# STM32F103ZGT6.net
KiCad netlist of a schematic drawn in Altium Designer
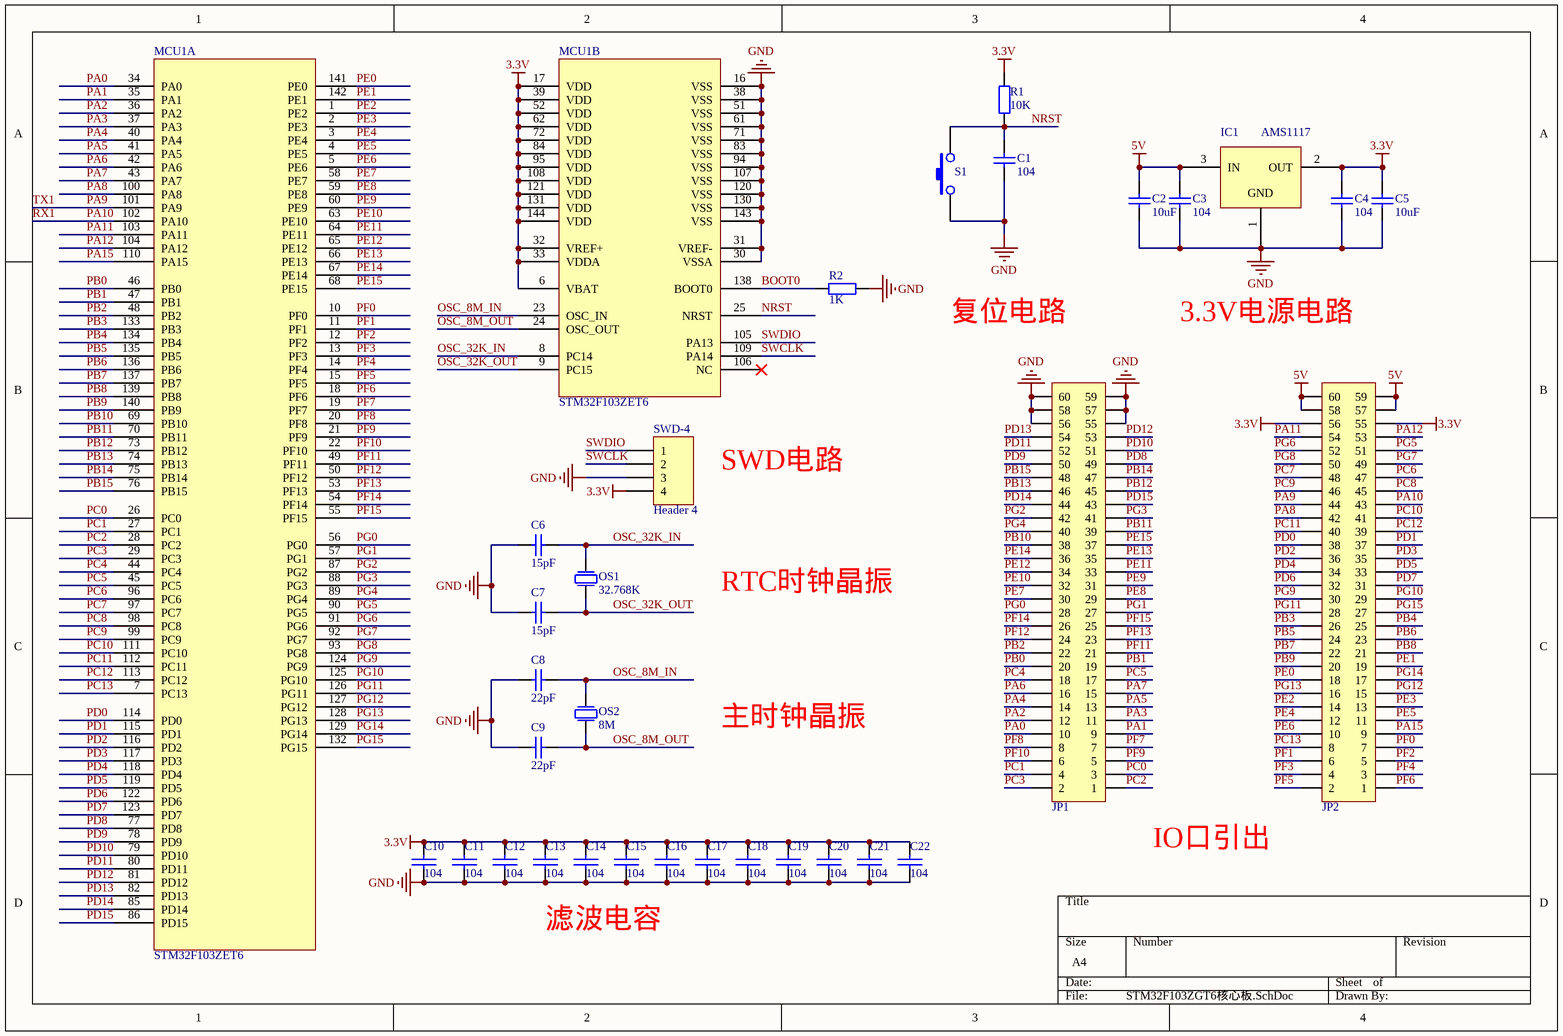
[diagram p0: STM32F103ZGT6核心板.SchDoc]

(export (version "E")
  (design (tool "Eeschema 10.0.6"))
  (components
    (comp (ref "C1") (value "104") (footprint "C 0603_L") (libsource (lib "零散元件库") (part "Cap1")))
    (comp (ref "C2") (value "10uF") (footprint "C 0603_L") (libsource (lib "零散元件库") (part "Cap1")))
    (comp (ref "C3") (value "104") (footprint "C 0603_L") (libsource (lib "零散元件库") (part "Cap1")))
    (comp (ref "C4") (value "104") (footprint "C 0603_L") (libsource (lib "零散元件库") (part "Cap1")))
    (comp (ref "C5") (value "10uF") (footprint "C 0603_L") (libsource (lib "零散元件库") (part "Cap1")))
    (comp (ref "C6") (value "15pF") (footprint "C 0603_L") (libsource (lib "零散元件库") (part "Cap1")))
    (comp (ref "C7") (value "15pF") (footprint "C 0603_L") (libsource (lib "零散元件库") (part "Cap1")))
    (comp (ref "C8") (value "22pF") (footprint "C 0603_L") (libsource (lib "零散元件库") (part "Cap1")))
    (comp (ref "C9") (value "22pF") (footprint "C 0603_L") (libsource (lib "零散元件库") (part "Cap1")))
    (comp (ref "C10")
      (value "104")
      (footprint "C 0603_L")
      (description "Capacitor")
      (libsource (lib "*") (part "CAP"))
    )
    (comp (ref "C11")
      (value "104")
      (footprint "C 0603_L")
      (description "Capacitor")
      (libsource (lib "*") (part "CAP"))
    )
    (comp (ref "C12")
      (value "104")
      (footprint "C 0603_L")
      (description "Capacitor")
      (libsource (lib "*") (part "CAP"))
    )
    (comp (ref "C13")
      (value "104")
      (footprint "C 0603_L")
      (description "Capacitor")
      (libsource (lib "*") (part "CAP"))
    )
    (comp (ref "C14")
      (value "104")
      (footprint "C 0603_L")
      (description "Capacitor")
      (libsource (lib "*") (part "CAP"))
    )
    (comp (ref "C15")
      (value "104")
      (footprint "C 0603_L")
      (description "Capacitor")
      (libsource (lib "*") (part "CAP"))
    )
    (comp (ref "C16")
      (value "104")
      (footprint "C 0603_L")
      (description "Capacitor")
      (libsource (lib "*") (part "CAP"))
    )
    (comp (ref "C17")
      (value "104")
      (footprint "C 0603_L")
      (description "Capacitor")
      (libsource (lib "*") (part "CAP"))
    )
    (comp (ref "C18")
      (value "104")
      (footprint "C 0603_L")
      (description "Capacitor")
      (libsource (lib "*") (part "CAP"))
    )
    (comp (ref "C19")
      (value "104")
      (footprint "C 0603_L")
      (description "Capacitor")
      (libsource (lib "*") (part "CAP"))
    )
    (comp (ref "C20")
      (value "104")
      (footprint "C 0603_L")
      (description "Capacitor")
      (libsource (lib "*") (part "CAP"))
    )
    (comp (ref "C21")
      (value "104")
      (footprint "C 0603_L")
      (description "Capacitor")
      (libsource (lib "*") (part "CAP"))
    )
    (comp (ref "C22")
      (value "104")
      (footprint "C 0603_L")
      (description "Capacitor")
      (libsource (lib "*") (part "CAP"))
    )
    (comp (ref "IC1") (value "AMS1117") (footprint "SOT89") (libsource (lib "零散元件库") (part "CJA1117")))
    (comp (ref "JP1")
      (value "Header 2X30")
      (footprint "HDR-SMD_60P-P1.27-V-M-R2-C30-LS5.8")
      (description "30*2P接插件")
      (fields (field (name "版权归属") "封装库来自淘宝 ID：黄晶宝石"))
      (libsource (lib "5.4 - 接插件-脚距2.54 (100mil) ") (part "Header 30X2"))
    )
    (comp (ref "JP2")
      (value "Header 2X30")
      (footprint "HDR-SMD_60P-P1.27-V-M-R2-C30-LS5.8")
      (description "30*2P接插件")
      (fields (field (name "版权归属") "封装库来自淘宝 ID：黄晶宝石"))
      (libsource (lib "5.4 - 接插件-脚距2.54 (100mil) ") (part "Header 30X2"))
    )
    (comp (ref "MCU1")
      (value "STM32F103ZET6")
      (footprint "F-QFP20x20-G144/Z24N")
      (libsource (lib "零散元件库") (part "STM32F103ZET6"))
    )
    (comp (ref "OS1")
      (value "32.768K")
      (footprint "R 0805_M")
      (fields (field (name "VAULE") "32.768K"))
      (libsource (lib "零散元件库") (part "晶振"))
    )
    (comp (ref "OS2")
      (value "8M")
      (footprint "OSC 5032-2P")
      (fields (field (name "VAULE") "8M"))
      (libsource (lib "零散元件库") (part "晶振"))
    )
    (comp (ref "R1") (value "10K") (footprint "R 0603_L") (libsource (lib "") (part "Res_1")))
    (comp (ref "R2") (value "1K") (footprint "R 0603_L") (libsource (lib "零散元件库") (part "Res")))
    (comp (ref "S1") (value "KEY") (footprint "SWT3*4") (libsource (lib "CCDXPLIB") (part "KEY")))
    (comp (ref "SWD-4")
      (value "Header 4")
      (footprint "HDR1X4")
      (description "Header, 4-Pin")
      (fields (field (name "PUBLISHER") "Altium Limited"))
      (libsource (lib "Miscellaneous Connectors") (part "Header 4"))
    )
  )
  (nets
    (net (code "2") (name "/BOOT0") (class "Default")
      (node (ref "MCU1") (pin "138") (pinfunction "BOOT0_138") (pintype "passive"))
      (node (ref "R2") (pin "2") (pinfunction "2_2") (pintype "passive"))
    )
    (net (code "3") (name "/NRST") (class "Default")
      (node (ref "C1") (pin "2") (pinfunction "2_2") (pintype "passive"))
      (node (ref "MCU1") (pin "25") (pinfunction "NRST_25") (pintype "passive"))
      (node (ref "R1") (pin "1") (pinfunction "1_1") (pintype "passive"))
      (node (ref "S1") (pin "2") (pinfunction "2_2") (pintype "passive"))
    )
    (net (code "4") (name "/OSC_8M_IN") (class "Default")
      (node (ref "C8") (pin "1") (pinfunction "1_1") (pintype "passive"))
      (node (ref "MCU1") (pin "23") (pinfunction "OSC_IN_23") (pintype "passive"))
      (node (ref "OS2") (pin "1") (pinfunction "P1_1") (pintype "passive"))
    )
    (net (code "5") (name "/OSC_8M_OUT") (class "Default")
      (node (ref "C9") (pin "1") (pinfunction "1_1") (pintype "passive"))
      (node (ref "MCU1") (pin "24") (pinfunction "OSC_OUT_24") (pintype "passive"))
      (node (ref "OS2") (pin "2") (pinfunction "P2_2") (pintype "passive"))
    )
    (net (code "6") (name "/OSC_32K_IN") (class "Default")
      (node (ref "C6") (pin "1") (pinfunction "1_1") (pintype "passive"))
      (node (ref "MCU1") (pin "8") (pinfunction "PC14_8") (pintype "passive"))
      (node (ref "OS1") (pin "1") (pinfunction "P1_1") (pintype "passive"))
    )
    (net (code "7") (name "/OSC_32K_OUT") (class "Default")
      (node (ref "C7") (pin "1") (pinfunction "1_1") (pintype "passive"))
      (node (ref "MCU1") (pin "9") (pinfunction "PC15_9") (pintype "passive"))
      (node (ref "OS1") (pin "2") (pinfunction "P2_2") (pintype "passive"))
    )
    (net (code "8") (name "/PA0") (class "Default")
      (node (ref "JP1") (pin "10") (pinfunction "10_10") (pintype "passive"))
      (node (ref "MCU1") (pin "34") (pinfunction "PA0_34") (pintype "passive"))
    )
    (net (code "9") (name "/PA1") (class "Default")
      (node (ref "JP1") (pin "9") (pinfunction "9_9") (pintype "passive"))
      (node (ref "MCU1") (pin "35") (pinfunction "PA1_35") (pintype "passive"))
    )
    (net (code "10") (name "/PA2") (class "Default")
      (node (ref "JP1") (pin "12") (pinfunction "12_12") (pintype "passive"))
      (node (ref "MCU1") (pin "36") (pinfunction "PA2_36") (pintype "passive"))
    )
    (net (code "11") (name "/PA3") (class "Default")
      (node (ref "JP1") (pin "11") (pinfunction "11_11") (pintype "passive"))
      (node (ref "MCU1") (pin "37") (pinfunction "PA3_37") (pintype "passive"))
    )
    (net (code "12") (name "/PA4") (class "Default")
      (node (ref "JP1") (pin "14") (pinfunction "14_14") (pintype "passive"))
      (node (ref "MCU1") (pin "40") (pinfunction "PA4_40") (pintype "passive"))
    )
    (net (code "13") (name "/PA5") (class "Default")
      (node (ref "JP1") (pin "13") (pinfunction "13_13") (pintype "passive"))
      (node (ref "MCU1") (pin "41") (pinfunction "PA5_41") (pintype "passive"))
    )
    (net (code "14") (name "/PA6") (class "Default")
      (node (ref "JP1") (pin "16") (pinfunction "16_16") (pintype "passive"))
      (node (ref "MCU1") (pin "42") (pinfunction "PA6_42") (pintype "passive"))
    )
    (net (code "15") (name "/PA7") (class "Default")
      (node (ref "JP1") (pin "15") (pinfunction "15_15") (pintype "passive"))
      (node (ref "MCU1") (pin "43") (pinfunction "PA7_43") (pintype "passive"))
    )
    (net (code "16") (name "/PA8") (class "Default")
      (node (ref "JP2") (pin "42") (pinfunction "42_42") (pintype "passive"))
      (node (ref "MCU1") (pin "100") (pinfunction "PA8_100") (pintype "passive"))
    )
    (net (code "17") (name "/PA9") (class "Default")
      (node (ref "JP2") (pin "44") (pinfunction "44_44") (pintype "passive"))
      (node (ref "MCU1") (pin "101") (pinfunction "PA9_101") (pintype "passive"))
    )
    (net (code "18") (name "/PA10") (class "Default")
      (node (ref "JP2") (pin "43") (pinfunction "43_43") (pintype "passive"))
      (node (ref "MCU1") (pin "102") (pinfunction "PA10_102") (pintype "passive"))
    )
    (net (code "19") (name "/PA11") (class "Default")
      (node (ref "JP2") (pin "54") (pinfunction "54_54") (pintype "passive"))
      (node (ref "MCU1") (pin "103") (pinfunction "PA11_103") (pintype "passive"))
    )
    (net (code "20") (name "/PA12") (class "Default")
      (node (ref "JP2") (pin "53") (pinfunction "53_53") (pintype "passive"))
      (node (ref "MCU1") (pin "104") (pinfunction "PA12_104") (pintype "passive"))
    )
    (net (code "21") (name "/PA15") (class "Default")
      (node (ref "JP2") (pin "9") (pinfunction "9_9") (pintype "passive"))
      (node (ref "MCU1") (pin "110") (pinfunction "PA15_110") (pintype "passive"))
    )
    (net (code "22") (name "/PB0") (class "Default")
      (node (ref "JP1") (pin "20") (pinfunction "20_20") (pintype "passive"))
      (node (ref "MCU1") (pin "46") (pinfunction "PB0_46") (pintype "passive"))
    )
    (net (code "23") (name "/PB1") (class "Default")
      (node (ref "JP1") (pin "19") (pinfunction "19_19") (pintype "passive"))
      (node (ref "MCU1") (pin "47") (pinfunction "PB1_47") (pintype "passive"))
    )
    (net (code "24") (name "/PB2") (class "Default")
      (node (ref "JP1") (pin "22") (pinfunction "22_22") (pintype "passive"))
      (node (ref "MCU1") (pin "48") (pinfunction "PB2_48") (pintype "passive"))
    )
    (net (code "25") (name "/PB3") (class "Default")
      (node (ref "JP2") (pin "26") (pinfunction "26_26") (pintype "passive"))
      (node (ref "MCU1") (pin "133") (pinfunction "PB3_133") (pintype "passive"))
    )
    (net (code "26") (name "/PB4") (class "Default")
      (node (ref "JP2") (pin "25") (pinfunction "25_25") (pintype "passive"))
      (node (ref "MCU1") (pin "134") (pinfunction "PB4_134") (pintype "passive"))
    )
    (net (code "27") (name "/PB5") (class "Default")
      (node (ref "JP2") (pin "24") (pinfunction "24_24") (pintype "passive"))
      (node (ref "MCU1") (pin "135") (pinfunction "PB5_135") (pintype "passive"))
    )
    (net (code "28") (name "/PB6") (class "Default")
      (node (ref "JP2") (pin "23") (pinfunction "23_23") (pintype "passive"))
      (node (ref "MCU1") (pin "136") (pinfunction "PB6_136") (pintype "passive"))
    )
    (net (code "29") (name "/PB7") (class "Default")
      (node (ref "JP2") (pin "22") (pinfunction "22_22") (pintype "passive"))
      (node (ref "MCU1") (pin "137") (pinfunction "PB7_137") (pintype "passive"))
    )
    (net (code "30") (name "/PB8") (class "Default")
      (node (ref "JP2") (pin "21") (pinfunction "21_21") (pintype "passive"))
      (node (ref "MCU1") (pin "139") (pinfunction "PB8_139") (pintype "passive"))
    )
    (net (code "31") (name "/PB9") (class "Default")
      (node (ref "JP2") (pin "20") (pinfunction "20_20") (pintype "passive"))
      (node (ref "MCU1") (pin "140") (pinfunction "PB9_140") (pintype "passive"))
    )
    (net (code "32") (name "/PB10") (class "Default")
      (node (ref "JP1") (pin "38") (pinfunction "38_38") (pintype "passive"))
      (node (ref "MCU1") (pin "69") (pinfunction "PB10_69") (pintype "passive"))
    )
    (net (code "33") (name "/PB11") (class "Default")
      (node (ref "JP1") (pin "39") (pinfunction "39_39") (pintype "passive"))
      (node (ref "MCU1") (pin "70") (pinfunction "PB11_70") (pintype "passive"))
    )
    (net (code "34") (name "/PB12") (class "Default")
      (node (ref "JP1") (pin "45") (pinfunction "45_45") (pintype "passive"))
      (node (ref "MCU1") (pin "73") (pinfunction "PB12_73") (pintype "passive"))
    )
    (net (code "35") (name "/PB13") (class "Default")
      (node (ref "JP1") (pin "46") (pinfunction "46_46") (pintype "passive"))
      (node (ref "MCU1") (pin "74") (pinfunction "PB13_74") (pintype "passive"))
    )
    (net (code "36") (name "/PB14") (class "Default")
      (node (ref "JP1") (pin "47") (pinfunction "47_47") (pintype "passive"))
      (node (ref "MCU1") (pin "75") (pinfunction "PB14_75") (pintype "passive"))
    )
    (net (code "37") (name "/PB15") (class "Default")
      (node (ref "JP1") (pin "48") (pinfunction "48_48") (pintype "passive"))
      (node (ref "MCU1") (pin "76") (pinfunction "PB15_76") (pintype "passive"))
    )
    (net (code "38") (name "/PC0") (class "Default")
      (node (ref "JP1") (pin "3") (pinfunction "3_3") (pintype "passive"))
      (node (ref "MCU1") (pin "26") (pinfunction "PC0_26") (pintype "passive"))
    )
    (net (code "39") (name "/PC1") (class "Default")
      (node (ref "JP1") (pin "4") (pinfunction "4_4") (pintype "passive"))
      (node (ref "MCU1") (pin "27") (pinfunction "PC1_27") (pintype "passive"))
    )
    (net (code "40") (name "/PC2") (class "Default")
      (node (ref "JP1") (pin "1") (pinfunction "1_1") (pintype "passive"))
      (node (ref "MCU1") (pin "28") (pinfunction "PC2_28") (pintype "passive"))
    )
    (net (code "41") (name "/PC3") (class "Default")
      (node (ref "JP1") (pin "2") (pinfunction "2_2") (pintype "passive"))
      (node (ref "MCU1") (pin "29") (pinfunction "PC3_29") (pintype "passive"))
    )
    (net (code "42") (name "/PC4") (class "Default")
      (node (ref "JP1") (pin "18") (pinfunction "18_18") (pintype "passive"))
      (node (ref "MCU1") (pin "44") (pinfunction "PC4_44") (pintype "passive"))
    )
    (net (code "43") (name "/PC5") (class "Default")
      (node (ref "JP1") (pin "17") (pinfunction "17_17") (pintype "passive"))
      (node (ref "MCU1") (pin "45") (pinfunction "PC5_45") (pintype "passive"))
    )
    (net (code "44") (name "/PC6") (class "Default")
      (node (ref "JP2") (pin "47") (pinfunction "47_47") (pintype "passive"))
      (node (ref "MCU1") (pin "96") (pinfunction "PC6_96") (pintype "passive"))
    )
    (net (code "45") (name "/PC7") (class "Default")
      (node (ref "JP2") (pin "48") (pinfunction "48_48") (pintype "passive"))
      (node (ref "MCU1") (pin "97") (pinfunction "PC7_97") (pintype "passive"))
    )
    (net (code "46") (name "/PC8") (class "Default")
      (node (ref "JP2") (pin "45") (pinfunction "45_45") (pintype "passive"))
      (node (ref "MCU1") (pin "98") (pinfunction "PC8_98") (pintype "passive"))
    )
    (net (code "47") (name "/PC9") (class "Default")
      (node (ref "JP2") (pin "46") (pinfunction "46_46") (pintype "passive"))
      (node (ref "MCU1") (pin "99") (pinfunction "PC9_99") (pintype "passive"))
    )
    (net (code "48") (name "/PC10") (class "Default")
      (node (ref "JP2") (pin "41") (pinfunction "41_41") (pintype "passive"))
      (node (ref "MCU1") (pin "111") (pinfunction "PC10_111") (pintype "passive"))
    )
    (net (code "49") (name "/PC11") (class "Default")
      (node (ref "JP2") (pin "40") (pinfunction "40_40") (pintype "passive"))
      (node (ref "MCU1") (pin "112") (pinfunction "PC11_112") (pintype "passive"))
    )
    (net (code "50") (name "/PC12") (class "Default")
      (node (ref "JP2") (pin "39") (pinfunction "39_39") (pintype "passive"))
      (node (ref "MCU1") (pin "113") (pinfunction "PC12_113") (pintype "passive"))
    )
    (net (code "51") (name "/PC13") (class "Default")
      (node (ref "JP2") (pin "8") (pinfunction "8_8") (pintype "passive"))
      (node (ref "MCU1") (pin "7") (pinfunction "PC13_7") (pintype "passive"))
    )
    (net (code "52") (name "/PD0") (class "Default")
      (node (ref "JP2") (pin "38") (pinfunction "38_38") (pintype "passive"))
      (node (ref "MCU1") (pin "114") (pinfunction "PD0_114") (pintype "passive"))
    )
    (net (code "53") (name "/PD1") (class "Default")
      (node (ref "JP2") (pin "37") (pinfunction "37_37") (pintype "passive"))
      (node (ref "MCU1") (pin "115") (pinfunction "PD1_115") (pintype "passive"))
    )
    (net (code "54") (name "/PD2") (class "Default")
      (node (ref "JP2") (pin "36") (pinfunction "36_36") (pintype "passive"))
      (node (ref "MCU1") (pin "116") (pinfunction "PD2_116") (pintype "passive"))
    )
    (net (code "55") (name "/PD3") (class "Default")
      (node (ref "JP2") (pin "35") (pinfunction "35_35") (pintype "passive"))
      (node (ref "MCU1") (pin "117") (pinfunction "PD3_117") (pintype "passive"))
    )
    (net (code "56") (name "/PD4") (class "Default")
      (node (ref "JP2") (pin "34") (pinfunction "34_34") (pintype "passive"))
      (node (ref "MCU1") (pin "118") (pinfunction "PD4_118") (pintype "passive"))
    )
    (net (code "57") (name "/PD5") (class "Default")
      (node (ref "JP2") (pin "33") (pinfunction "33_33") (pintype "passive"))
      (node (ref "MCU1") (pin "119") (pinfunction "PD5_119") (pintype "passive"))
    )
    (net (code "58") (name "/PD6") (class "Default")
      (node (ref "JP2") (pin "32") (pinfunction "32_32") (pintype "passive"))
      (node (ref "MCU1") (pin "122") (pinfunction "PD6_122") (pintype "passive"))
    )
    (net (code "59") (name "/PD7") (class "Default")
      (node (ref "JP2") (pin "31") (pinfunction "31_31") (pintype "passive"))
      (node (ref "MCU1") (pin "123") (pinfunction "PD7_123") (pintype "passive"))
    )
    (net (code "60") (name "/PD8") (class "Default")
      (node (ref "JP1") (pin "49") (pinfunction "49_49") (pintype "passive"))
      (node (ref "MCU1") (pin "77") (pinfunction "PD8_77") (pintype "passive"))
    )
    (net (code "61") (name "/PD9") (class "Default")
      (node (ref "JP1") (pin "50") (pinfunction "50_50") (pintype "passive"))
      (node (ref "MCU1") (pin "78") (pinfunction "PD9_78") (pintype "passive"))
    )
    (net (code "62") (name "/PD10") (class "Default")
      (node (ref "JP1") (pin "51") (pinfunction "51_51") (pintype "passive"))
      (node (ref "MCU1") (pin "79") (pinfunction "PD10_79") (pintype "passive"))
    )
    (net (code "63") (name "/PD11") (class "Default")
      (node (ref "JP1") (pin "52") (pinfunction "52_52") (pintype "passive"))
      (node (ref "MCU1") (pin "80") (pinfunction "PD11_80") (pintype "passive"))
    )
    (net (code "64") (name "/PD12") (class "Default")
      (node (ref "JP1") (pin "53") (pinfunction "53_53") (pintype "passive"))
      (node (ref "MCU1") (pin "81") (pinfunction "PD12_81") (pintype "passive"))
    )
    (net (code "65") (name "/PD13") (class "Default")
      (node (ref "JP1") (pin "54") (pinfunction "54_54") (pintype "passive"))
      (node (ref "MCU1") (pin "82") (pinfunction "PD13_82") (pintype "passive"))
    )
    (net (code "66") (name "/PD14") (class "Default")
      (node (ref "JP1") (pin "44") (pinfunction "44_44") (pintype "passive"))
      (node (ref "MCU1") (pin "85") (pinfunction "PD14_85") (pintype "passive"))
    )
    (net (code "67") (name "/PD15") (class "Default")
      (node (ref "JP1") (pin "43") (pinfunction "43_43") (pintype "passive"))
      (node (ref "MCU1") (pin "86") (pinfunction "PD15_86") (pintype "passive"))
    )
    (net (code "68") (name "/PE0") (class "Default")
      (node (ref "JP2") (pin "18") (pinfunction "18_18") (pintype "passive"))
      (node (ref "MCU1") (pin "141") (pinfunction "PE0_141") (pintype "passive"))
    )
    (net (code "69") (name "/PE1") (class "Default")
      (node (ref "JP2") (pin "19") (pinfunction "19_19") (pintype "passive"))
      (node (ref "MCU1") (pin "142") (pinfunction "PE1_142") (pintype "passive"))
    )
    (net (code "70") (name "/PE2") (class "Default")
      (node (ref "JP2") (pin "14") (pinfunction "14_14") (pintype "passive"))
      (node (ref "MCU1") (pin "1") (pinfunction "PE2_1") (pintype "passive"))
    )
    (net (code "71") (name "/PE3") (class "Default")
      (node (ref "JP2") (pin "13") (pinfunction "13_13") (pintype "passive"))
      (node (ref "MCU1") (pin "2") (pinfunction "PE3_2") (pintype "passive"))
    )
    (net (code "72") (name "/PE4") (class "Default")
      (node (ref "JP2") (pin "12") (pinfunction "12_12") (pintype "passive"))
      (node (ref "MCU1") (pin "3") (pinfunction "PE4_3") (pintype "passive"))
    )
    (net (code "73") (name "/PE5") (class "Default")
      (node (ref "JP2") (pin "11") (pinfunction "11_11") (pintype "passive"))
      (node (ref "MCU1") (pin "4") (pinfunction "PE5_4") (pintype "passive"))
    )
    (net (code "74") (name "/PE6") (class "Default")
      (node (ref "JP2") (pin "10") (pinfunction "10_10") (pintype "passive"))
      (node (ref "MCU1") (pin "5") (pinfunction "PE6_5") (pintype "passive"))
    )
    (net (code "75") (name "/PE7") (class "Default")
      (node (ref "JP1") (pin "30") (pinfunction "30_30") (pintype "passive"))
      (node (ref "MCU1") (pin "58") (pinfunction "PE7_58") (pintype "passive"))
    )
    (net (code "76") (name "/PE8") (class "Default")
      (node (ref "JP1") (pin "29") (pinfunction "29_29") (pintype "passive"))
      (node (ref "MCU1") (pin "59") (pinfunction "PE8_59") (pintype "passive"))
    )
    (net (code "77") (name "/PE9") (class "Default")
      (node (ref "JP1") (pin "31") (pinfunction "31_31") (pintype "passive"))
      (node (ref "MCU1") (pin "60") (pinfunction "PE9_60") (pintype "passive"))
    )
    (net (code "78") (name "/PE10") (class "Default")
      (node (ref "JP1") (pin "32") (pinfunction "32_32") (pintype "passive"))
      (node (ref "MCU1") (pin "63") (pinfunction "PE10_63") (pintype "passive"))
    )
    (net (code "79") (name "/PE11") (class "Default")
      (node (ref "JP1") (pin "33") (pinfunction "33_33") (pintype "passive"))
      (node (ref "MCU1") (pin "64") (pinfunction "PE11_64") (pintype "passive"))
    )
    (net (code "80") (name "/PE12") (class "Default")
      (node (ref "JP1") (pin "34") (pinfunction "34_34") (pintype "passive"))
      (node (ref "MCU1") (pin "65") (pinfunction "PE12_65") (pintype "passive"))
    )
    (net (code "81") (name "/PE13") (class "Default")
      (node (ref "JP1") (pin "35") (pinfunction "35_35") (pintype "passive"))
      (node (ref "MCU1") (pin "66") (pinfunction "PE13_66") (pintype "passive"))
    )
    (net (code "82") (name "/PE14") (class "Default")
      (node (ref "JP1") (pin "36") (pinfunction "36_36") (pintype "passive"))
      (node (ref "MCU1") (pin "67") (pinfunction "PE14_67") (pintype "passive"))
    )
    (net (code "83") (name "/PE15") (class "Default")
      (node (ref "JP1") (pin "37") (pinfunction "37_37") (pintype "passive"))
      (node (ref "MCU1") (pin "68") (pinfunction "PE15_68") (pintype "passive"))
    )
    (net (code "84") (name "/PF0") (class "Default")
      (node (ref "JP2") (pin "7") (pinfunction "7_7") (pintype "passive"))
      (node (ref "MCU1") (pin "10") (pinfunction "PF0_10") (pintype "passive"))
    )
    (net (code "85") (name "/PF1") (class "Default")
      (node (ref "JP2") (pin "6") (pinfunction "6_6") (pintype "passive"))
      (node (ref "MCU1") (pin "11") (pinfunction "PF1_11") (pintype "passive"))
    )
    (net (code "86") (name "/PF2") (class "Default")
      (node (ref "JP2") (pin "5") (pinfunction "5_5") (pintype "passive"))
      (node (ref "MCU1") (pin "12") (pinfunction "PF2_12") (pintype "passive"))
    )
    (net (code "87") (name "/PF3") (class "Default")
      (node (ref "JP2") (pin "4") (pinfunction "4_4") (pintype "passive"))
      (node (ref "MCU1") (pin "13") (pinfunction "PF3_13") (pintype "passive"))
    )
    (net (code "88") (name "/PF4") (class "Default")
      (node (ref "JP2") (pin "3") (pinfunction "3_3") (pintype "passive"))
      (node (ref "MCU1") (pin "14") (pinfunction "PF4_14") (pintype "passive"))
    )
    (net (code "89") (name "/PF5") (class "Default")
      (node (ref "JP2") (pin "2") (pinfunction "2_2") (pintype "passive"))
      (node (ref "MCU1") (pin "15") (pinfunction "PF5_15") (pintype "passive"))
    )
    (net (code "90") (name "/PF6") (class "Default")
      (node (ref "JP2") (pin "1") (pinfunction "1_1") (pintype "passive"))
      (node (ref "MCU1") (pin "18") (pinfunction "PF6_18") (pintype "passive"))
    )
    (net (code "91") (name "/PF7") (class "Default")
      (node (ref "JP1") (pin "7") (pinfunction "7_7") (pintype "passive"))
      (node (ref "MCU1") (pin "19") (pinfunction "PF7_19") (pintype "passive"))
    )
    (net (code "92") (name "/PF8") (class "Default")
      (node (ref "JP1") (pin "8") (pinfunction "8_8") (pintype "passive"))
      (node (ref "MCU1") (pin "20") (pinfunction "PF8_20") (pintype "passive"))
    )
    (net (code "93") (name "/PF9") (class "Default")
      (node (ref "JP1") (pin "5") (pinfunction "5_5") (pintype "passive"))
      (node (ref "MCU1") (pin "21") (pinfunction "PF9_21") (pintype "passive"))
    )
    (net (code "94") (name "/PF10") (class "Default")
      (node (ref "JP1") (pin "6") (pinfunction "6_6") (pintype "passive"))
      (node (ref "MCU1") (pin "22") (pinfunction "PF10_22") (pintype "passive"))
    )
    (net (code "95") (name "/PF11") (class "Default")
      (node (ref "JP1") (pin "21") (pinfunction "21_21") (pintype "passive"))
      (node (ref "MCU1") (pin "49") (pinfunction "PF11_49") (pintype "passive"))
    )
    (net (code "96") (name "/PF12") (class "Default")
      (node (ref "JP1") (pin "24") (pinfunction "24_24") (pintype "passive"))
      (node (ref "MCU1") (pin "50") (pinfunction "PF12_50") (pintype "passive"))
    )
    (net (code "97") (name "/PF13") (class "Default")
      (node (ref "JP1") (pin "23") (pinfunction "23_23") (pintype "passive"))
      (node (ref "MCU1") (pin "53") (pinfunction "PF13_53") (pintype "passive"))
    )
    (net (code "98") (name "/PF14") (class "Default")
      (node (ref "JP1") (pin "26") (pinfunction "26_26") (pintype "passive"))
      (node (ref "MCU1") (pin "54") (pinfunction "PF14_54") (pintype "passive"))
    )
    (net (code "99") (name "/PF15") (class "Default")
      (node (ref "JP1") (pin "25") (pinfunction "25_25") (pintype "passive"))
      (node (ref "MCU1") (pin "55") (pinfunction "PF15_55") (pintype "passive"))
    )
    (net (code "100") (name "/PG0") (class "Default")
      (node (ref "JP1") (pin "28") (pinfunction "28_28") (pintype "passive"))
      (node (ref "MCU1") (pin "56") (pinfunction "PG0_56") (pintype "passive"))
    )
    (net (code "101") (name "/PG1") (class "Default")
      (node (ref "JP1") (pin "27") (pinfunction "27_27") (pintype "passive"))
      (node (ref "MCU1") (pin "57") (pinfunction "PG1_57") (pintype "passive"))
    )
    (net (code "102") (name "/PG2") (class "Default")
      (node (ref "JP1") (pin "42") (pinfunction "42_42") (pintype "passive"))
      (node (ref "MCU1") (pin "87") (pinfunction "PG2_87") (pintype "passive"))
    )
    (net (code "103") (name "/PG3") (class "Default")
      (node (ref "JP1") (pin "41") (pinfunction "41_41") (pintype "passive"))
      (node (ref "MCU1") (pin "88") (pinfunction "PG3_88") (pintype "passive"))
    )
    (net (code "104") (name "/PG4") (class "Default")
      (node (ref "JP1") (pin "40") (pinfunction "40_40") (pintype "passive"))
      (node (ref "MCU1") (pin "89") (pinfunction "PG4_89") (pintype "passive"))
    )
    (net (code "105") (name "/PG5") (class "Default")
      (node (ref "JP2") (pin "51") (pinfunction "51_51") (pintype "passive"))
      (node (ref "MCU1") (pin "90") (pinfunction "PG5_90") (pintype "passive"))
    )
    (net (code "106") (name "/PG6") (class "Default")
      (node (ref "JP2") (pin "52") (pinfunction "52_52") (pintype "passive"))
      (node (ref "MCU1") (pin "91") (pinfunction "PG6_91") (pintype "passive"))
    )
    (net (code "107") (name "/PG7") (class "Default")
      (node (ref "JP2") (pin "49") (pinfunction "49_49") (pintype "passive"))
      (node (ref "MCU1") (pin "92") (pinfunction "PG7_92") (pintype "passive"))
    )
    (net (code "108") (name "/PG8") (class "Default")
      (node (ref "JP2") (pin "50") (pinfunction "50_50") (pintype "passive"))
      (node (ref "MCU1") (pin "93") (pinfunction "PG8_93") (pintype "passive"))
    )
    (net (code "109") (name "/PG9") (class "Default")
      (node (ref "JP2") (pin "30") (pinfunction "30_30") (pintype "passive"))
      (node (ref "MCU1") (pin "124") (pinfunction "PG9_124") (pintype "passive"))
    )
    (net (code "110") (name "/PG10") (class "Default")
      (node (ref "JP2") (pin "29") (pinfunction "29_29") (pintype "passive"))
      (node (ref "MCU1") (pin "125") (pinfunction "PG10_125") (pintype "passive"))
    )
    (net (code "111") (name "/PG11") (class "Default")
      (node (ref "JP2") (pin "28") (pinfunction "28_28") (pintype "passive"))
      (node (ref "MCU1") (pin "126") (pinfunction "PG11_126") (pintype "passive"))
    )
    (net (code "112") (name "/PG12") (class "Default")
      (node (ref "JP2") (pin "15") (pinfunction "15_15") (pintype "passive"))
      (node (ref "MCU1") (pin "127") (pinfunction "PG12_127") (pintype "passive"))
    )
    (net (code "113") (name "/PG13") (class "Default")
      (node (ref "JP2") (pin "16") (pinfunction "16_16") (pintype "passive"))
      (node (ref "MCU1") (pin "128") (pinfunction "PG13_128") (pintype "passive"))
    )
    (net (code "114") (name "/PG14") (class "Default")
      (node (ref "JP2") (pin "17") (pinfunction "17_17") (pintype "passive"))
      (node (ref "MCU1") (pin "129") (pinfunction "PG14_129") (pintype "passive"))
    )
    (net (code "115") (name "/PG15") (class "Default")
      (node (ref "JP2") (pin "27") (pinfunction "27_27") (pintype "passive"))
      (node (ref "MCU1") (pin "132") (pinfunction "PG15_132") (pintype "passive"))
    )
    (net (code "116") (name "/SWCLK") (class "Default")
      (node (ref "MCU1") (pin "109") (pinfunction "PA14_109") (pintype "passive"))
      (node (ref "SWD-4") (pin "2") (pinfunction "2_2") (pintype "passive"))
    )
    (net (code "117") (name "/SWDIO") (class "Default")
      (node (ref "MCU1") (pin "105") (pinfunction "PA13_105") (pintype "passive"))
      (node (ref "SWD-4") (pin "1") (pinfunction "1_1") (pintype "passive"))
    )
    (net (code "118") (name "3.3V") (class "Default")
      (node (ref "C10") (pin "1") (pinfunction "1_1") (pintype "passive"))
      (node (ref "C11") (pin "1") (pinfunction "1_1") (pintype "passive"))
      (node (ref "C12") (pin "1") (pinfunction "1_1") (pintype "passive"))
      (node (ref "C13") (pin "1") (pinfunction "1_1") (pintype "passive"))
      (node (ref "C14") (pin "1") (pinfunction "1_1") (pintype "passive"))
      (node (ref "C15") (pin "1") (pinfunction "1_1") (pintype "passive"))
      (node (ref "C16") (pin "1") (pinfunction "1_1") (pintype "passive"))
      (node (ref "C17") (pin "1") (pinfunction "1_1") (pintype "passive"))
      (node (ref "C18") (pin "1") (pinfunction "1_1") (pintype "passive"))
      (node (ref "C19") (pin "1") (pinfunction "1_1") (pintype "passive"))
      (node (ref "C20") (pin "1") (pinfunction "1_1") (pintype "passive"))
      (node (ref "C21") (pin "1") (pinfunction "1_1") (pintype "passive"))
      (node (ref "C22") (pin "1") (pinfunction "1_1") (pintype "passive"))
      (node (ref "C4") (pin "2") (pinfunction "2_2") (pintype "passive"))
      (node (ref "C5") (pin "2") (pinfunction "2_2") (pintype "passive"))
      (node (ref "IC1") (pin "2") (pinfunction "OUT_2") (pintype "passive"))
      (node (ref "JP2") (pin "55") (pinfunction "55_55") (pintype "passive"))
      (node (ref "JP2") (pin "56") (pinfunction "56_56") (pintype "passive"))
      (node (ref "MCU1") (pin "108") (pinfunction "VDD_108") (pintype "passive"))
      (node (ref "MCU1") (pin "121") (pinfunction "VDD_121") (pintype "passive"))
      (node (ref "MCU1") (pin "131") (pinfunction "VDD_131") (pintype "passive"))
      (node (ref "MCU1") (pin "144") (pinfunction "VDD_144") (pintype "passive"))
      (node (ref "MCU1") (pin "17") (pinfunction "VDD_17") (pintype "passive"))
      (node (ref "MCU1") (pin "32") (pinfunction "VREF+_32") (pintype "passive"))
      (node (ref "MCU1") (pin "33") (pinfunction "VDDA_33") (pintype "passive"))
      (node (ref "MCU1") (pin "39") (pinfunction "VDD_39") (pintype "passive"))
      (node (ref "MCU1") (pin "52") (pinfunction "VDD_52") (pintype "passive"))
      (node (ref "MCU1") (pin "6") (pinfunction "VBAT_6") (pintype "passive"))
      (node (ref "MCU1") (pin "62") (pinfunction "VDD_62") (pintype "passive"))
      (node (ref "MCU1") (pin "72") (pinfunction "VDD_72") (pintype "passive"))
      (node (ref "MCU1") (pin "84") (pinfunction "VDD_84") (pintype "passive"))
      (node (ref "MCU1") (pin "95") (pinfunction "VDD_95") (pintype "passive"))
      (node (ref "R1") (pin "2") (pinfunction "2_2") (pintype "passive"))
      (node (ref "SWD-4") (pin "4") (pinfunction "4_4") (pintype "passive"))
    )
    (net (code "119") (name "5V") (class "Default")
      (node (ref "C2") (pin "2") (pinfunction "2_2") (pintype "passive"))
      (node (ref "C3") (pin "2") (pinfunction "2_2") (pintype "passive"))
      (node (ref "IC1") (pin "3") (pinfunction "IN_3") (pintype "passive"))
      (node (ref "JP2") (pin "57") (pinfunction "57_57") (pintype "passive"))
      (node (ref "JP2") (pin "58") (pinfunction "58_58") (pintype "passive"))
      (node (ref "JP2") (pin "59") (pinfunction "59_59") (pintype "passive"))
      (node (ref "JP2") (pin "60") (pinfunction "60_60") (pintype "passive"))
    )
    (net (code "120") (name "GND") (class "Default")
      (node (ref "C1") (pin "1") (pinfunction "1_1") (pintype "passive"))
      (node (ref "C10") (pin "2") (pinfunction "2_2") (pintype "passive"))
      (node (ref "C11") (pin "2") (pinfunction "2_2") (pintype "passive"))
      (node (ref "C12") (pin "2") (pinfunction "2_2") (pintype "passive"))
      (node (ref "C13") (pin "2") (pinfunction "2_2") (pintype "passive"))
      (node (ref "C14") (pin "2") (pinfunction "2_2") (pintype "passive"))
      (node (ref "C15") (pin "2") (pinfunction "2_2") (pintype "passive"))
      (node (ref "C16") (pin "2") (pinfunction "2_2") (pintype "passive"))
      (node (ref "C17") (pin "2") (pinfunction "2_2") (pintype "passive"))
      (node (ref "C18") (pin "2") (pinfunction "2_2") (pintype "passive"))
      (node (ref "C19") (pin "2") (pinfunction "2_2") (pintype "passive"))
      (node (ref "C2") (pin "1") (pinfunction "1_1") (pintype "passive"))
      (node (ref "C20") (pin "2") (pinfunction "2_2") (pintype "passive"))
      (node (ref "C21") (pin "2") (pinfunction "2_2") (pintype "passive"))
      (node (ref "C22") (pin "2") (pinfunction "2_2") (pintype "passive"))
      (node (ref "C3") (pin "1") (pinfunction "1_1") (pintype "passive"))
      (node (ref "C4") (pin "1") (pinfunction "1_1") (pintype "passive"))
      (node (ref "C5") (pin "1") (pinfunction "1_1") (pintype "passive"))
      (node (ref "C6") (pin "2") (pinfunction "2_2") (pintype "passive"))
      (node (ref "C7") (pin "2") (pinfunction "2_2") (pintype "passive"))
      (node (ref "C8") (pin "2") (pinfunction "2_2") (pintype "passive"))
      (node (ref "C9") (pin "2") (pinfunction "2_2") (pintype "passive"))
      (node (ref "IC1") (pin "1") (pinfunction "GND_1") (pintype "passive"))
      (node (ref "JP1") (pin "55") (pinfunction "55_55") (pintype "passive"))
      (node (ref "JP1") (pin "56") (pinfunction "56_56") (pintype "passive"))
      (node (ref "JP1") (pin "57") (pinfunction "57_57") (pintype "passive"))
      (node (ref "JP1") (pin "58") (pinfunction "58_58") (pintype "passive"))
      (node (ref "JP1") (pin "59") (pinfunction "59_59") (pintype "passive"))
      (node (ref "JP1") (pin "60") (pinfunction "60_60") (pintype "passive"))
      (node (ref "MCU1") (pin "107") (pinfunction "VSS_107") (pintype "passive"))
      (node (ref "MCU1") (pin "120") (pinfunction "VSS_120") (pintype "passive"))
      (node (ref "MCU1") (pin "130") (pinfunction "VSS_130") (pintype "passive"))
      (node (ref "MCU1") (pin "143") (pinfunction "VSS_143") (pintype "passive"))
      (node (ref "MCU1") (pin "16") (pinfunction "VSS_16") (pintype "passive"))
      (node (ref "MCU1") (pin "30") (pinfunction "VSSA_30") (pintype "passive"))
      (node (ref "MCU1") (pin "31") (pinfunction "VREF-_31") (pintype "passive"))
      (node (ref "MCU1") (pin "38") (pinfunction "VSS_38") (pintype "passive"))
      (node (ref "MCU1") (pin "51") (pinfunction "VSS_51") (pintype "passive"))
      (node (ref "MCU1") (pin "61") (pinfunction "VSS_61") (pintype "passive"))
      (node (ref "MCU1") (pin "71") (pinfunction "VSS_71") (pintype "passive"))
      (node (ref "MCU1") (pin "83") (pinfunction "VSS_83") (pintype "passive"))
      (node (ref "MCU1") (pin "94") (pinfunction "VSS_94") (pintype "passive"))
      (node (ref "R2") (pin "1") (pinfunction "1_1") (pintype "passive"))
      (node (ref "S1") (pin "1") (pinfunction "1_1") (pintype "passive"))
      (node (ref "SWD-4") (pin "3") (pinfunction "3_3") (pintype "passive"))
    )
    (net (code "121") (name "unconnected-(MCU1B-NC-Pad106)") (class "Default")
      (node (ref "MCU1") (pin "106") (pinfunction "NC_106") (pintype "passive+no_connect"))
    )
  )
)
